# cyberdriver.net
KiCad netlist of a schematic drawn in EAGLE
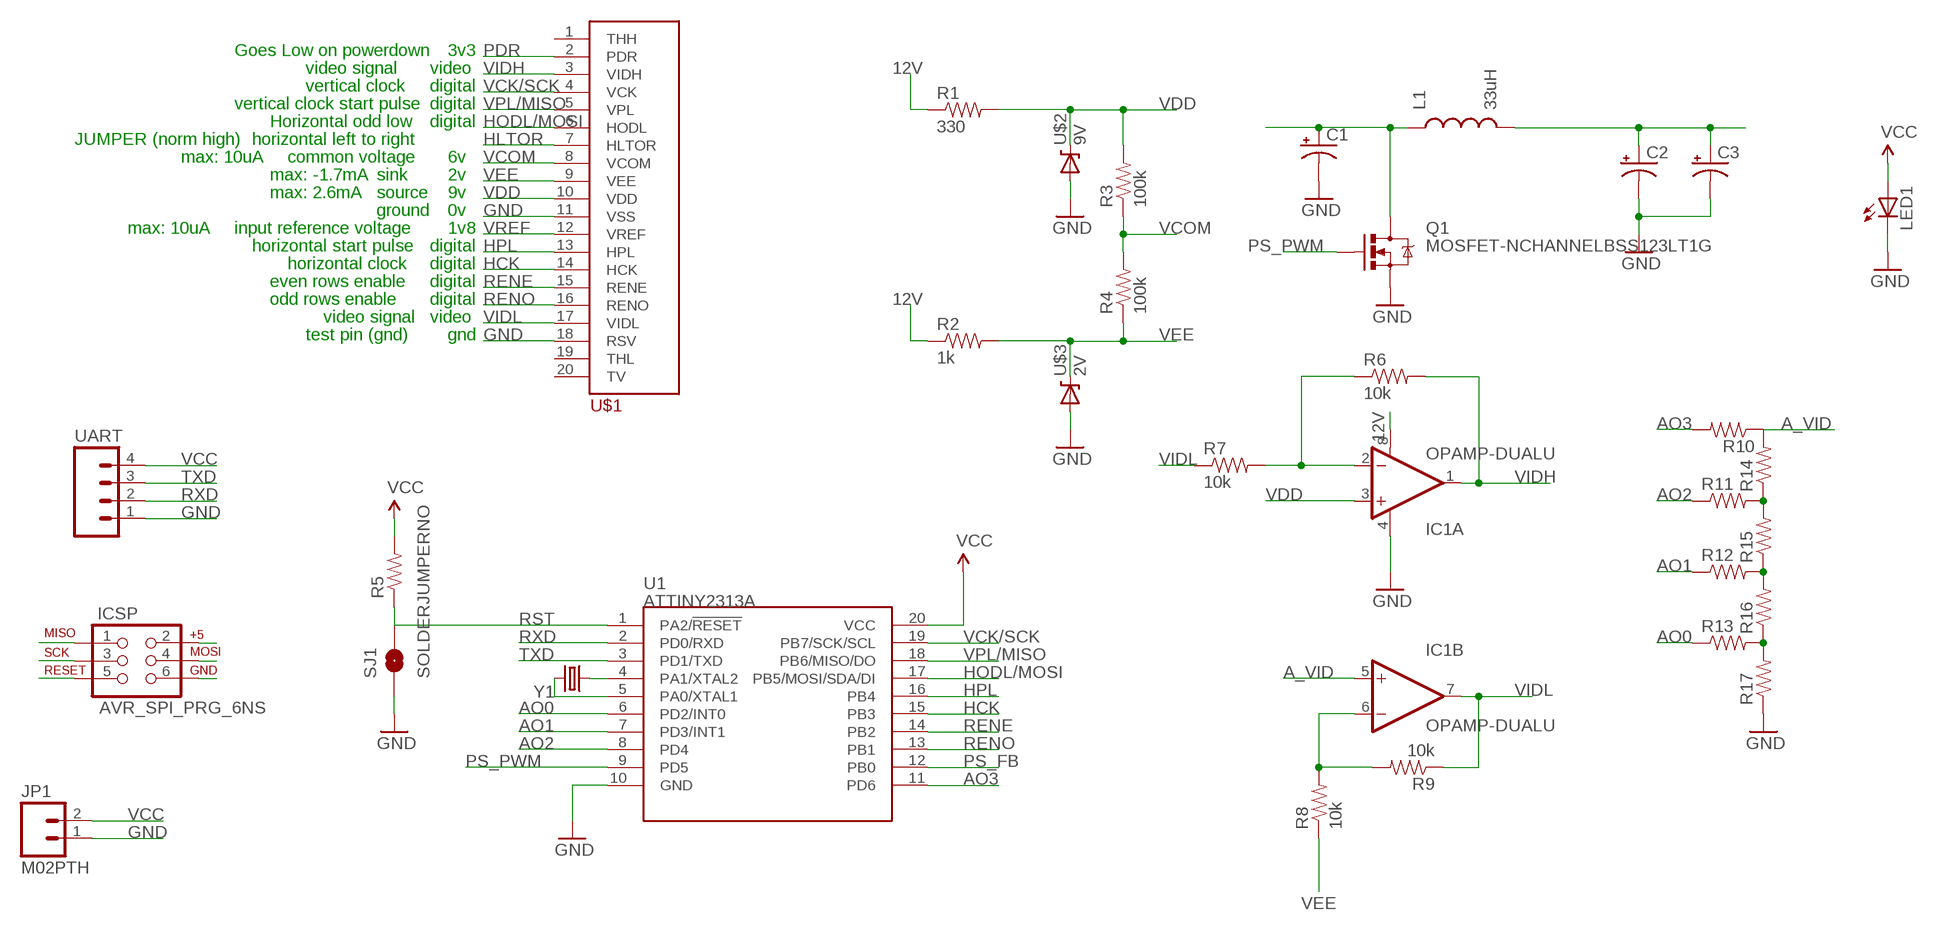
[diagram p0: schematic, sheet 1]

(export (version "E")
  (design (tool "Eeschema 10.0.6"))
  (components
    (comp (ref "C1")
      (value "CAP_POLC")
      (footprint "eagle-import:PANASONIC_C")
      (libsource (lib "eagle-import") (part "CAP_POLC"))
    )
    (comp (ref "C2")
      (value "CAP_POLC")
      (footprint "eagle-import:PANASONIC_C")
      (libsource (lib "eagle-import") (part "CAP_POLC"))
    )
    (comp (ref "C3")
      (value "CAP_POL1206")
      (footprint "eagle-import:EIA3216")
      (libsource (lib "eagle-import") (part "CAP_POL1206"))
    )
    (comp (ref "IC1")
      (value "OPAMP-DUALU")
      (footprint "eagle-import:SO08@1")
      (libsource (lib "eagle-import") (part "OPAMP-DUALU"))
    )
    (comp (ref "ICSP")
      (value "AVR_SPI_PRG_6NS")
      (footprint "eagle-import:2X3-NS")
      (libsource (lib "eagle-import") (part "AVR_SPI_PRG_6NS"))
    )
    (comp (ref "JP1")
      (value "M02PTH")
      (footprint "eagle-import:1X02")
      (libsource (lib "eagle-import") (part "M02PTH"))
    )
    (comp (ref "L1")
      (value "33uH")
      (footprint "eagle-import:SRN6045")
      (libsource (lib "eagle-import") (part "INDUCTORBOURNS_SRN6045"))
    )
    (comp (ref "LED1")
      (value "LED1206")
      (footprint "eagle-import:LED-1206")
      (libsource (lib "eagle-import") (part "LED1206"))
    )
    (comp (ref "Q1")
      (value "MOSFET-NCHANNELBSS123LT1G")
      (footprint "eagle-import:SOT23")
      (libsource (lib "eagle-import") (part "MOSFET-NCHANNELBSS123LT1G"))
    )
    (comp (ref "R1")
      (value "330")
      (footprint "eagle-import:0603-RES")
      (libsource (lib "eagle-import") (part "RESISTOR0603-RES"))
    )
    (comp (ref "R2")
      (value "1k")
      (footprint "eagle-import:0603-RES")
      (libsource (lib "eagle-import") (part "RESISTOR0603-RES"))
    )
    (comp (ref "R3")
      (value "100k")
      (footprint "eagle-import:0805")
      (libsource (lib "eagle-import") (part "RESISTOR0805-RES"))
    )
    (comp (ref "R4")
      (value "100k")
      (footprint "eagle-import:0805")
      (libsource (lib "eagle-import") (part "RESISTOR0805-RES"))
    )
    (comp (ref "R5")
      (value "RESISTOR0805-RES")
      (footprint "eagle-import:0805")
      (libsource (lib "eagle-import") (part "RESISTOR0805-RES"))
    )
    (comp (ref "R6")
      (value "10k")
      (footprint "eagle-import:0805")
      (libsource (lib "eagle-import") (part "RESISTOR0805-RES"))
    )
    (comp (ref "R7")
      (value "10k")
      (footprint "eagle-import:0805")
      (libsource (lib "eagle-import") (part "RESISTOR0805-RES"))
    )
    (comp (ref "R8")
      (value "10k")
      (footprint "eagle-import:0805")
      (libsource (lib "eagle-import") (part "RESISTOR0805-RES"))
    )
    (comp (ref "R9")
      (value "10k")
      (footprint "eagle-import:0805")
      (libsource (lib "eagle-import") (part "RESISTOR0805-RES"))
    )
    (comp (ref "R10")
      (value "RESISTOR0805-RES")
      (footprint "eagle-import:0805")
      (libsource (lib "eagle-import") (part "RESISTOR0805-RES"))
    )
    (comp (ref "R11")
      (value "RESISTOR0805-RES")
      (footprint "eagle-import:0805")
      (libsource (lib "eagle-import") (part "RESISTOR0805-RES"))
    )
    (comp (ref "R12")
      (value "RESISTOR0805-RES")
      (footprint "eagle-import:0805")
      (libsource (lib "eagle-import") (part "RESISTOR0805-RES"))
    )
    (comp (ref "R13")
      (value "RESISTOR0805-RES")
      (footprint "eagle-import:0805")
      (libsource (lib "eagle-import") (part "RESISTOR0805-RES"))
    )
    (comp (ref "R14")
      (value "RESISTOR0805-RES")
      (footprint "eagle-import:0805")
      (libsource (lib "eagle-import") (part "RESISTOR0805-RES"))
    )
    (comp (ref "R15")
      (value "RESISTOR0805-RES")
      (footprint "eagle-import:0805")
      (libsource (lib "eagle-import") (part "RESISTOR0805-RES"))
    )
    (comp (ref "R16")
      (value "RESISTOR0805-RES")
      (footprint "eagle-import:0805")
      (libsource (lib "eagle-import") (part "RESISTOR0805-RES"))
    )
    (comp (ref "R17")
      (value "RESISTOR0805-RES")
      (footprint "eagle-import:0805")
      (libsource (lib "eagle-import") (part "RESISTOR0805-RES"))
    )
    (comp (ref "SJ1")
      (value "SOLDERJUMPERNO")
      (footprint "eagle-import:SJ_2S-NO")
      (libsource (lib "eagle-import") (part "SOLDERJUMPERNO"))
    )
    (comp (ref "U$1")
      (value "CYBERDISPLAY-CONN")
      (footprint "eagle-import:MOLEX-54550-2071")
      (libsource (lib "eagle-import") (part "CYBERDISPLAY-CONN"))
    )
    (comp (ref "U$2")
      (value "9V")
      (footprint "eagle-import:SOD-323")
      (libsource (lib "eagle-import") (part "DIODE-ZENER-BZT52"))
    )
    (comp (ref "U$3")
      (value "2V")
      (footprint "eagle-import:SOD-323")
      (libsource (lib "eagle-import") (part "DIODE-ZENER-BZT52"))
    )
    (comp (ref "U1")
      (value "ATTINY2313A")
      (footprint "eagle-import:SOP20W")
      (libsource (lib "eagle-import") (part "ATTINY2313A"))
    )
    (comp (ref "UART")
      (value "M04PTH")
      (footprint "eagle-import:1X04")
      (libsource (lib "eagle-import") (part "M04PTH"))
    )
    (comp (ref "Y1")
      (value "CRYSTAL5X3")
      (footprint "eagle-import:CRYSTAL-SMD-5X3")
      (libsource (lib "eagle-import") (part "CRYSTAL5X3"))
    )
  )
  (nets
    (net (code "1") (name "/12V") (class "Default")
      (node (ref "C2") (pin "+") (pinfunction "+_+") (pintype "passive"))
      (node (ref "C3") (pin "A") (pinfunction "+_A") (pintype "passive"))
      (node (ref "IC1") (pin "8") (pinfunction "V+_8") (pintype "power_in"))
      (node (ref "L1") (pin "2") (pinfunction "2_2") (pintype "passive"))
      (node (ref "R1") (pin "1") (pinfunction "1_1") (pintype "passive"))
      (node (ref "R2") (pin "1") (pinfunction "1_1") (pintype "passive"))
    )
    (net (code "2") (name "/AO0") (class "Default")
      (node (ref "R13") (pin "1") (pinfunction "1_1") (pintype "passive"))
      (node (ref "U1") (pin "6") (pinfunction "PD2/INT0_6") (pintype "bidirectional"))
    )
    (net (code "3") (name "/AO1") (class "Default")
      (node (ref "R12") (pin "1") (pinfunction "1_1") (pintype "passive"))
      (node (ref "U1") (pin "7") (pinfunction "PD3/INT1_7") (pintype "bidirectional"))
    )
    (net (code "4") (name "/AO2") (class "Default")
      (node (ref "R11") (pin "1") (pinfunction "1_1") (pintype "passive"))
      (node (ref "U1") (pin "8") (pinfunction "PD4_8") (pintype "bidirectional"))
    )
    (net (code "5") (name "/AO3") (class "Default")
      (node (ref "R10") (pin "2") (pinfunction "2_2") (pintype "passive"))
      (node (ref "U1") (pin "11") (pinfunction "PD6_11") (pintype "bidirectional"))
    )
    (net (code "6") (name "/A_VID") (class "Default")
      (node (ref "IC1") (pin "5") (pinfunction "+IN_5") (pintype "input"))
      (node (ref "R10") (pin "1") (pinfunction "1_1") (pintype "passive"))
      (node (ref "R14") (pin "2") (pinfunction "2_2") (pintype "passive"))
    )
    (net (code "7") (name "/HCK") (class "Default")
      (node (ref "U$1") (pin "14") (pinfunction "HCK_14") (pintype "bidirectional"))
      (node (ref "U1") (pin "15") (pinfunction "PB3_15") (pintype "bidirectional"))
    )
    (net (code "8") (name "/HLTOR") (class "Default")
      (node (ref "U$1") (pin "7") (pinfunction "HLTOR_7") (pintype "bidirectional"))
    )
    (net (code "9") (name "/HODL{slash}MOSI") (class "Default")
      (node (ref "ICSP") (pin "4") (pinfunction "4_4") (pintype "passive"))
      (node (ref "U$1") (pin "6") (pinfunction "HODL_6") (pintype "bidirectional"))
      (node (ref "U1") (pin "17") (pinfunction "PB5/MOSI/SDA/DI_17") (pintype "bidirectional"))
    )
    (net (code "10") (name "/HPL") (class "Default")
      (node (ref "U$1") (pin "13") (pinfunction "HPL_13") (pintype "bidirectional"))
      (node (ref "U1") (pin "16") (pinfunction "PB4_16") (pintype "bidirectional"))
    )
    (net (code "11") (name "/PDR") (class "Default")
      (node (ref "U$1") (pin "2") (pinfunction "PDR_2") (pintype "bidirectional"))
    )
    (net (code "12") (name "/PS_FB") (class "Default")
      (node (ref "U1") (pin "12") (pinfunction "PB0_12") (pintype "bidirectional"))
    )
    (net (code "13") (name "/PS_PWM") (class "Default")
      (node (ref "Q1") (pin "1") (pinfunction "G_1") (pintype "passive"))
      (node (ref "U1") (pin "9") (pinfunction "PD5_9") (pintype "bidirectional"))
    )
    (net (code "14") (name "/RENE") (class "Default")
      (node (ref "U$1") (pin "15") (pinfunction "RENE_15") (pintype "bidirectional"))
      (node (ref "U1") (pin "14") (pinfunction "PB2_14") (pintype "bidirectional"))
    )
    (net (code "15") (name "/RENO") (class "Default")
      (node (ref "U$1") (pin "16") (pinfunction "RENO_16") (pintype "bidirectional"))
      (node (ref "U1") (pin "13") (pinfunction "PB1_13") (pintype "bidirectional"))
    )
    (net (code "16") (name "/RST") (class "Default")
      (node (ref "ICSP") (pin "5") (pinfunction "5_5") (pintype "passive"))
      (node (ref "R5") (pin "1") (pinfunction "1_1") (pintype "passive"))
      (node (ref "SJ1") (pin "2") (pinfunction "2_2") (pintype "passive"))
      (node (ref "U1") (pin "1") (pinfunction "PA2/~{RESET}_1") (pintype "bidirectional"))
    )
    (net (code "17") (name "/RXD") (class "Default")
      (node (ref "U1") (pin "2") (pinfunction "PD0/RXD_2") (pintype "bidirectional"))
      (node (ref "UART") (pin "2") (pinfunction "2_2") (pintype "passive"))
    )
    (net (code "18") (name "/TXD") (class "Default")
      (node (ref "U1") (pin "3") (pinfunction "PD1/TXD_3") (pintype "bidirectional"))
      (node (ref "UART") (pin "3") (pinfunction "3_3") (pintype "passive"))
    )
    (net (code "19") (name "/VCK{slash}SCK") (class "Default")
      (node (ref "ICSP") (pin "3") (pinfunction "3_3") (pintype "passive"))
      (node (ref "U$1") (pin "4") (pinfunction "VCK_4") (pintype "bidirectional"))
      (node (ref "U1") (pin "19") (pinfunction "PB7/SCK/SCL_19") (pintype "bidirectional"))
    )
    (net (code "20") (name "/VCOM") (class "Default")
      (node (ref "R3") (pin "1") (pinfunction "1_1") (pintype "passive"))
      (node (ref "R4") (pin "2") (pinfunction "2_2") (pintype "passive"))
      (node (ref "U$1") (pin "8") (pinfunction "VCOM_8") (pintype "bidirectional"))
    )
    (net (code "21") (name "/VDD") (class "Default")
      (node (ref "IC1") (pin "3") (pinfunction "+IN_3") (pintype "input"))
      (node (ref "R1") (pin "2") (pinfunction "2_2") (pintype "passive"))
      (node (ref "R3") (pin "2") (pinfunction "2_2") (pintype "passive"))
      (node (ref "U$1") (pin "10") (pinfunction "VDD_10") (pintype "bidirectional"))
      (node (ref "U$2") (pin "C") (pinfunction "C_C") (pintype "passive"))
    )
    (net (code "22") (name "/VEE") (class "Default")
      (node (ref "R2") (pin "2") (pinfunction "2_2") (pintype "passive"))
      (node (ref "R4") (pin "1") (pinfunction "1_1") (pintype "passive"))
      (node (ref "R8") (pin "1") (pinfunction "1_1") (pintype "passive"))
      (node (ref "U$1") (pin "9") (pinfunction "VEE_9") (pintype "bidirectional"))
      (node (ref "U$3") (pin "C") (pinfunction "C_C") (pintype "passive"))
    )
    (net (code "23") (name "/VIDH") (class "Default")
      (node (ref "IC1") (pin "1") (pinfunction "OUT_1") (pintype "output"))
      (node (ref "R6") (pin "2") (pinfunction "2_2") (pintype "passive"))
      (node (ref "U$1") (pin "3") (pinfunction "VIDH_3") (pintype "bidirectional"))
    )
    (net (code "24") (name "/VIDL") (class "Default")
      (node (ref "IC1") (pin "7") (pinfunction "OUT_7") (pintype "output"))
      (node (ref "R7") (pin "1") (pinfunction "1_1") (pintype "passive"))
      (node (ref "R9") (pin "1") (pinfunction "1_1") (pintype "passive"))
      (node (ref "U$1") (pin "17") (pinfunction "VIDL_17") (pintype "bidirectional"))
    )
    (net (code "25") (name "/VPL{slash}MISO") (class "Default")
      (node (ref "ICSP") (pin "1") (pinfunction "1_1") (pintype "passive"))
      (node (ref "U$1") (pin "5") (pinfunction "VPL_5") (pintype "bidirectional"))
      (node (ref "U1") (pin "18") (pinfunction "PB6/MISO/DO_18") (pintype "bidirectional"))
    )
    (net (code "26") (name "/VREF") (class "Default")
      (node (ref "U$1") (pin "12") (pinfunction "VREF_12") (pintype "bidirectional"))
    )
    (net (code "27") (name "GND") (class "Default")
      (node (ref "C1") (pin "-") (pinfunction "-_-") (pintype "passive"))
      (node (ref "C2") (pin "-") (pinfunction "-_-") (pintype "passive"))
      (node (ref "C3") (pin "C") (pinfunction "-_C") (pintype "passive"))
      (node (ref "IC1") (pin "4") (pinfunction "V-_4") (pintype "power_in"))
      (node (ref "ICSP") (pin "6") (pinfunction "6_6") (pintype "passive"))
      (node (ref "JP1") (pin "1") (pinfunction "1_1") (pintype "passive"))
      (node (ref "LED1") (pin "C") (pinfunction "C_C") (pintype "passive"))
      (node (ref "Q1") (pin "2") (pinfunction "S_2") (pintype "passive"))
      (node (ref "R17") (pin "1") (pinfunction "1_1") (pintype "passive"))
      (node (ref "SJ1") (pin "1") (pinfunction "1_1") (pintype "passive"))
      (node (ref "U$1") (pin "11") (pinfunction "VSS_11") (pintype "bidirectional"))
      (node (ref "U$1") (pin "18") (pinfunction "RSV_18") (pintype "bidirectional"))
      (node (ref "U$2") (pin "A") (pinfunction "A_A") (pintype "passive"))
      (node (ref "U$3") (pin "A") (pinfunction "A_A") (pintype "passive"))
      (node (ref "U1") (pin "10") (pinfunction "GND_10") (pintype "bidirectional"))
      (node (ref "UART") (pin "1") (pinfunction "1_1") (pintype "passive"))
    )
    (net (code "28") (name "Net-(IC1A--IN)") (class "Default")
      (node (ref "IC1") (pin "2") (pinfunction "-IN_2") (pintype "input"))
      (node (ref "R6") (pin "1") (pinfunction "1_1") (pintype "passive"))
      (node (ref "R7") (pin "2") (pinfunction "2_2") (pintype "passive"))
    )
    (net (code "29") (name "Net-(IC1B--IN)") (class "Default")
      (node (ref "IC1") (pin "6") (pinfunction "-IN_6") (pintype "input"))
      (node (ref "R8") (pin "2") (pinfunction "2_2") (pintype "passive"))
      (node (ref "R9") (pin "2") (pinfunction "2_2") (pintype "passive"))
    )
    (net (code "30") (name "Net-(Q1-D)") (class "Default")
      (node (ref "C1") (pin "+") (pinfunction "+_+") (pintype "passive"))
      (node (ref "L1") (pin "1") (pinfunction "1_1") (pintype "passive"))
      (node (ref "Q1") (pin "3") (pinfunction "D_3") (pintype "passive"))
    )
    (net (code "31") (name "Net-(R11-Pad2)") (class "Default")
      (node (ref "R11") (pin "2") (pinfunction "2_2") (pintype "passive"))
      (node (ref "R14") (pin "1") (pinfunction "1_1") (pintype "passive"))
      (node (ref "R15") (pin "2") (pinfunction "2_2") (pintype "passive"))
    )
    (net (code "32") (name "Net-(R12-Pad2)") (class "Default")
      (node (ref "R12") (pin "2") (pinfunction "2_2") (pintype "passive"))
      (node (ref "R15") (pin "1") (pinfunction "1_1") (pintype "passive"))
      (node (ref "R16") (pin "2") (pinfunction "2_2") (pintype "passive"))
    )
    (net (code "33") (name "Net-(R13-Pad2)") (class "Default")
      (node (ref "R13") (pin "2") (pinfunction "2_2") (pintype "passive"))
      (node (ref "R16") (pin "1") (pinfunction "1_1") (pintype "passive"))
      (node (ref "R17") (pin "2") (pinfunction "2_2") (pintype "passive"))
    )
    (net (code "34") (name "Net-(U1-PA0{slash}XTAL1)") (class "Default")
      (node (ref "U1") (pin "5") (pinfunction "PA0/XTAL1_5") (pintype "bidirectional"))
      (node (ref "Y1") (pin "3") (pinfunction "2_3") (pintype "passive"))
    )
    (net (code "35") (name "Net-(U1-PA1{slash}XTAL2)") (class "Default")
      (node (ref "U1") (pin "4") (pinfunction "PA1/XTAL2_4") (pintype "bidirectional"))
      (node (ref "Y1") (pin "1") (pinfunction "1_1") (pintype "passive"))
    )
    (net (code "36") (name "VCC") (class "Default")
      (node (ref "ICSP") (pin "2") (pinfunction "2_2") (pintype "passive"))
      (node (ref "JP1") (pin "2") (pinfunction "2_2") (pintype "passive"))
      (node (ref "LED1") (pin "A") (pinfunction "A_A") (pintype "passive"))
      (node (ref "R5") (pin "2") (pinfunction "2_2") (pintype "passive"))
      (node (ref "U1") (pin "20") (pinfunction "VCC_20") (pintype "bidirectional"))
      (node (ref "UART") (pin "4") (pinfunction "4_4") (pintype "passive"))
    )
    (net (code "37") (name "unconnected-(U$1-THH-Pad1)") (class "Default")
      (node (ref "U$1") (pin "1") (pinfunction "THH_1") (pintype "bidirectional"))
    )
    (net (code "38") (name "unconnected-(U$1-THL-Pad19)") (class "Default")
      (node (ref "U$1") (pin "19") (pinfunction "THL_19") (pintype "bidirectional"))
    )
    (net (code "39") (name "unconnected-(U$1-TV-Pad20)") (class "Default")
      (node (ref "U$1") (pin "20") (pinfunction "TV_20") (pintype "bidirectional"))
    )
  )
)
